# FORCA-OHMICO.net
KiCad netlist of a schematic drawn in EAGLE
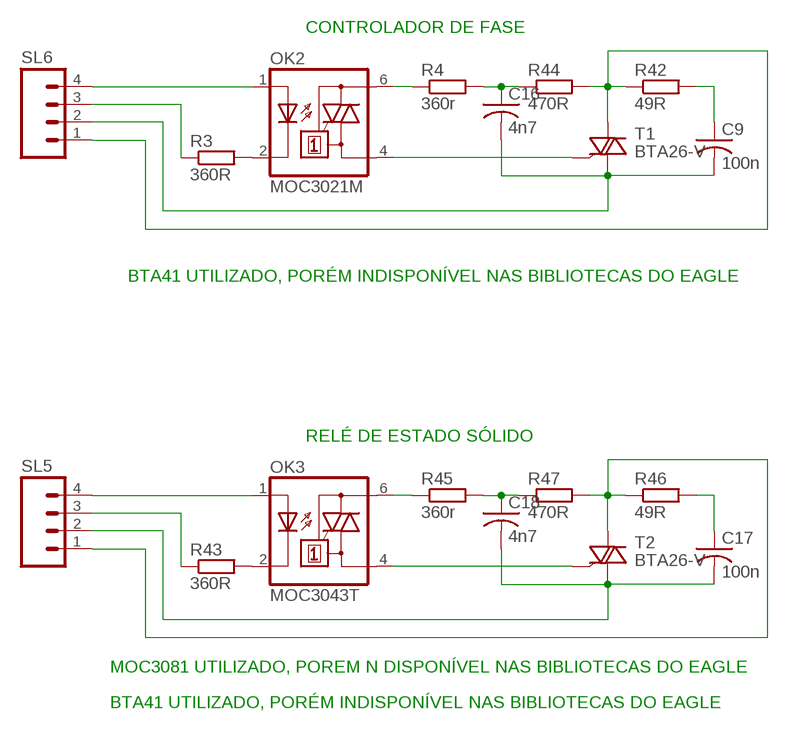
[diagram p0: schematic, sheet 2]

(export (version "E")
  (design (tool "Eeschema 10.0.6"))
  (components
    (comp (ref "C9")
      (value "100n")
      (footprint "eagle-import:C050-035X075")
      (libsource (lib "eagle-import") (part "C-US050-035X075"))
    )
    (comp (ref "C16")
      (value "4n7")
      (footprint "eagle-import:C050-035X075")
      (libsource (lib "eagle-import") (part "C-US050-035X075"))
    )
    (comp (ref "C17")
      (value "100n")
      (footprint "eagle-import:C050-035X075")
      (libsource (lib "eagle-import") (part "C-US050-035X075"))
    )
    (comp (ref "C18")
      (value "4n7")
      (footprint "eagle-import:C050-035X075")
      (libsource (lib "eagle-import") (part "C-US050-035X075"))
    )
    (comp (ref "OK2")
      (value "MOC3021M")
      (footprint "eagle-import:DIL06")
      (fields (field (name "MF") "FAIRCHILD SEMICONDUCTOR") (field (name "MPN") "MOC3021-M"))
      (libsource (lib "eagle-import") (part "MOC30M21"))
    )
    (comp (ref "OK3")
      (value "MOC3043T")
      (footprint "eagle-import:DIL06B")
      (fields (field (name "MF") "FAIRCHILD SEMICONDUCTOR") (field (name "MPN") "MOC3043TM"))
      (libsource (lib "eagle-import") (part "MOC30T43"))
    )
    (comp (ref "R3")
      (value "360R")
      (footprint "eagle-import:0207_10")
      (libsource (lib "eagle-import") (part "R-EU_0207/10"))
    )
    (comp (ref "R4")
      (value "360r")
      (footprint "eagle-import:0207_10")
      (libsource (lib "eagle-import") (part "R-EU_0207/10"))
    )
    (comp (ref "R42")
      (value "49R")
      (footprint "eagle-import:0207_10")
      (libsource (lib "eagle-import") (part "R-EU_0207/10"))
    )
    (comp (ref "R43")
      (value "360R")
      (footprint "eagle-import:0207_10")
      (libsource (lib "eagle-import") (part "R-EU_0207/10"))
    )
    (comp (ref "R44")
      (value "470R")
      (footprint "eagle-import:0309_12")
      (libsource (lib "eagle-import") (part "R-EU_0309/12"))
    )
    (comp (ref "R45")
      (value "360r")
      (footprint "eagle-import:0207_10")
      (libsource (lib "eagle-import") (part "R-EU_0207/10"))
    )
    (comp (ref "R46")
      (value "49R")
      (footprint "eagle-import:0207_10")
      (libsource (lib "eagle-import") (part "R-EU_0207/10"))
    )
    (comp (ref "R47")
      (value "470R")
      (footprint "eagle-import:0309_12")
      (libsource (lib "eagle-import") (part "R-EU_0309/12"))
    )
    (comp (ref "SL5")
      (value "M04")
      (footprint "eagle-import:04P")
      (libsource (lib "eagle-import") (part "M04"))
    )
    (comp (ref "SL6")
      (value "M04")
      (footprint "eagle-import:04P")
      (libsource (lib "eagle-import") (part "M04"))
    )
    (comp (ref "T1")
      (value "BTA26-V")
      (footprint "eagle-import:TOP3S-1")
      (libsource (lib "eagle-import") (part "BTA26-V"))
    )
    (comp (ref "T2")
      (value "BTA26-V")
      (footprint "eagle-import:TOP3S-1")
      (libsource (lib "eagle-import") (part "BTA26-V"))
    )
  )
  (nets
    (net (code "1") (name "Net-(C9-Pad1)") (class "Default")
      (node (ref "C9") (pin "1") (pinfunction "1_1") (pintype "passive"))
      (node (ref "R42") (pin "2") (pinfunction "2_2") (pintype "passive"))
    )
    (net (code "2") (name "Net-(C16-Pad1)") (class "Default")
      (node (ref "C16") (pin "1") (pinfunction "1_1") (pintype "passive"))
      (node (ref "R4") (pin "2") (pinfunction "2_2") (pintype "passive"))
      (node (ref "R44") (pin "1") (pinfunction "1_1") (pintype "passive"))
    )
    (net (code "3") (name "Net-(C16-Pad2)") (class "Default")
      (node (ref "C16") (pin "2") (pinfunction "2_2") (pintype "passive"))
      (node (ref "C9") (pin "2") (pinfunction "2_2") (pintype "passive"))
      (node (ref "SL6") (pin "2") (pinfunction "2_2") (pintype "passive"))
      (node (ref "T1") (pin "A1") (pinfunction "A1_A1") (pintype "passive"))
    )
    (net (code "4") (name "Net-(C17-Pad1)") (class "Default")
      (node (ref "C17") (pin "1") (pinfunction "1_1") (pintype "passive"))
      (node (ref "R46") (pin "2") (pinfunction "2_2") (pintype "passive"))
    )
    (net (code "5") (name "Net-(C17-Pad2)") (class "Default")
      (node (ref "C17") (pin "2") (pinfunction "2_2") (pintype "passive"))
      (node (ref "C18") (pin "2") (pinfunction "2_2") (pintype "passive"))
      (node (ref "SL5") (pin "2") (pinfunction "2_2") (pintype "passive"))
      (node (ref "T2") (pin "A1") (pinfunction "A1_A1") (pintype "passive"))
    )
    (net (code "6") (name "Net-(C18-Pad1)") (class "Default")
      (node (ref "C18") (pin "1") (pinfunction "1_1") (pintype "passive"))
      (node (ref "R45") (pin "2") (pinfunction "2_2") (pintype "passive"))
      (node (ref "R47") (pin "1") (pinfunction "1_1") (pintype "passive"))
    )
    (net (code "7") (name "Net-(OK2-A)") (class "Default")
      (node (ref "OK2") (pin "1") (pinfunction "A_1") (pintype "passive"))
      (node (ref "SL6") (pin "4") (pinfunction "4_4") (pintype "passive"))
    )
    (net (code "8") (name "Net-(OK2-A1)") (class "Default")
      (node (ref "OK2") (pin "4") (pinfunction "A1_4") (pintype "passive"))
      (node (ref "T1") (pin "G") (pinfunction "G_G") (pintype "passive"))
    )
    (net (code "9") (name "Net-(OK2-A2)") (class "Default")
      (node (ref "OK2") (pin "6") (pinfunction "A2_6") (pintype "passive"))
      (node (ref "R4") (pin "1") (pinfunction "1_1") (pintype "passive"))
    )
    (net (code "10") (name "Net-(OK2-C)") (class "Default")
      (node (ref "OK2") (pin "2") (pinfunction "C_2") (pintype "passive"))
      (node (ref "R3") (pin "2") (pinfunction "2_2") (pintype "passive"))
    )
    (net (code "11") (name "Net-(OK3-A)") (class "Default")
      (node (ref "OK3") (pin "1") (pinfunction "A_1") (pintype "passive"))
      (node (ref "SL5") (pin "4") (pinfunction "4_4") (pintype "passive"))
    )
    (net (code "12") (name "Net-(OK3-A1)") (class "Default")
      (node (ref "OK3") (pin "4") (pinfunction "A1_4") (pintype "passive"))
      (node (ref "T2") (pin "G") (pinfunction "G_G") (pintype "passive"))
    )
    (net (code "13") (name "Net-(OK3-A2)") (class "Default")
      (node (ref "OK3") (pin "6") (pinfunction "A2_6") (pintype "passive"))
      (node (ref "R45") (pin "1") (pinfunction "1_1") (pintype "passive"))
    )
    (net (code "14") (name "Net-(OK3-C)") (class "Default")
      (node (ref "OK3") (pin "2") (pinfunction "C_2") (pintype "passive"))
      (node (ref "R43") (pin "2") (pinfunction "2_2") (pintype "passive"))
    )
    (net (code "15") (name "Net-(R3-Pad1)") (class "Default")
      (node (ref "R3") (pin "1") (pinfunction "1_1") (pintype "passive"))
      (node (ref "SL6") (pin "3") (pinfunction "3_3") (pintype "passive"))
    )
    (net (code "16") (name "Net-(R42-Pad1)") (class "Default")
      (node (ref "R42") (pin "1") (pinfunction "1_1") (pintype "passive"))
      (node (ref "R44") (pin "2") (pinfunction "2_2") (pintype "passive"))
      (node (ref "SL6") (pin "1") (pinfunction "1_1") (pintype "passive"))
      (node (ref "T1") (pin "A2") (pinfunction "A2_A2") (pintype "passive"))
    )
    (net (code "17") (name "Net-(R43-Pad1)") (class "Default")
      (node (ref "R43") (pin "1") (pinfunction "1_1") (pintype "passive"))
      (node (ref "SL5") (pin "3") (pinfunction "3_3") (pintype "passive"))
    )
    (net (code "18") (name "Net-(R46-Pad1)") (class "Default")
      (node (ref "R46") (pin "1") (pinfunction "1_1") (pintype "passive"))
      (node (ref "R47") (pin "2") (pinfunction "2_2") (pintype "passive"))
      (node (ref "SL5") (pin "1") (pinfunction "1_1") (pintype "passive"))
      (node (ref "T2") (pin "A2") (pinfunction "A2_A2") (pintype "passive"))
    )
  )
)
